# mbedUSBBorderRouter-V_1_0_0.net
KiCad netlist of a schematic drawn in EAGLE
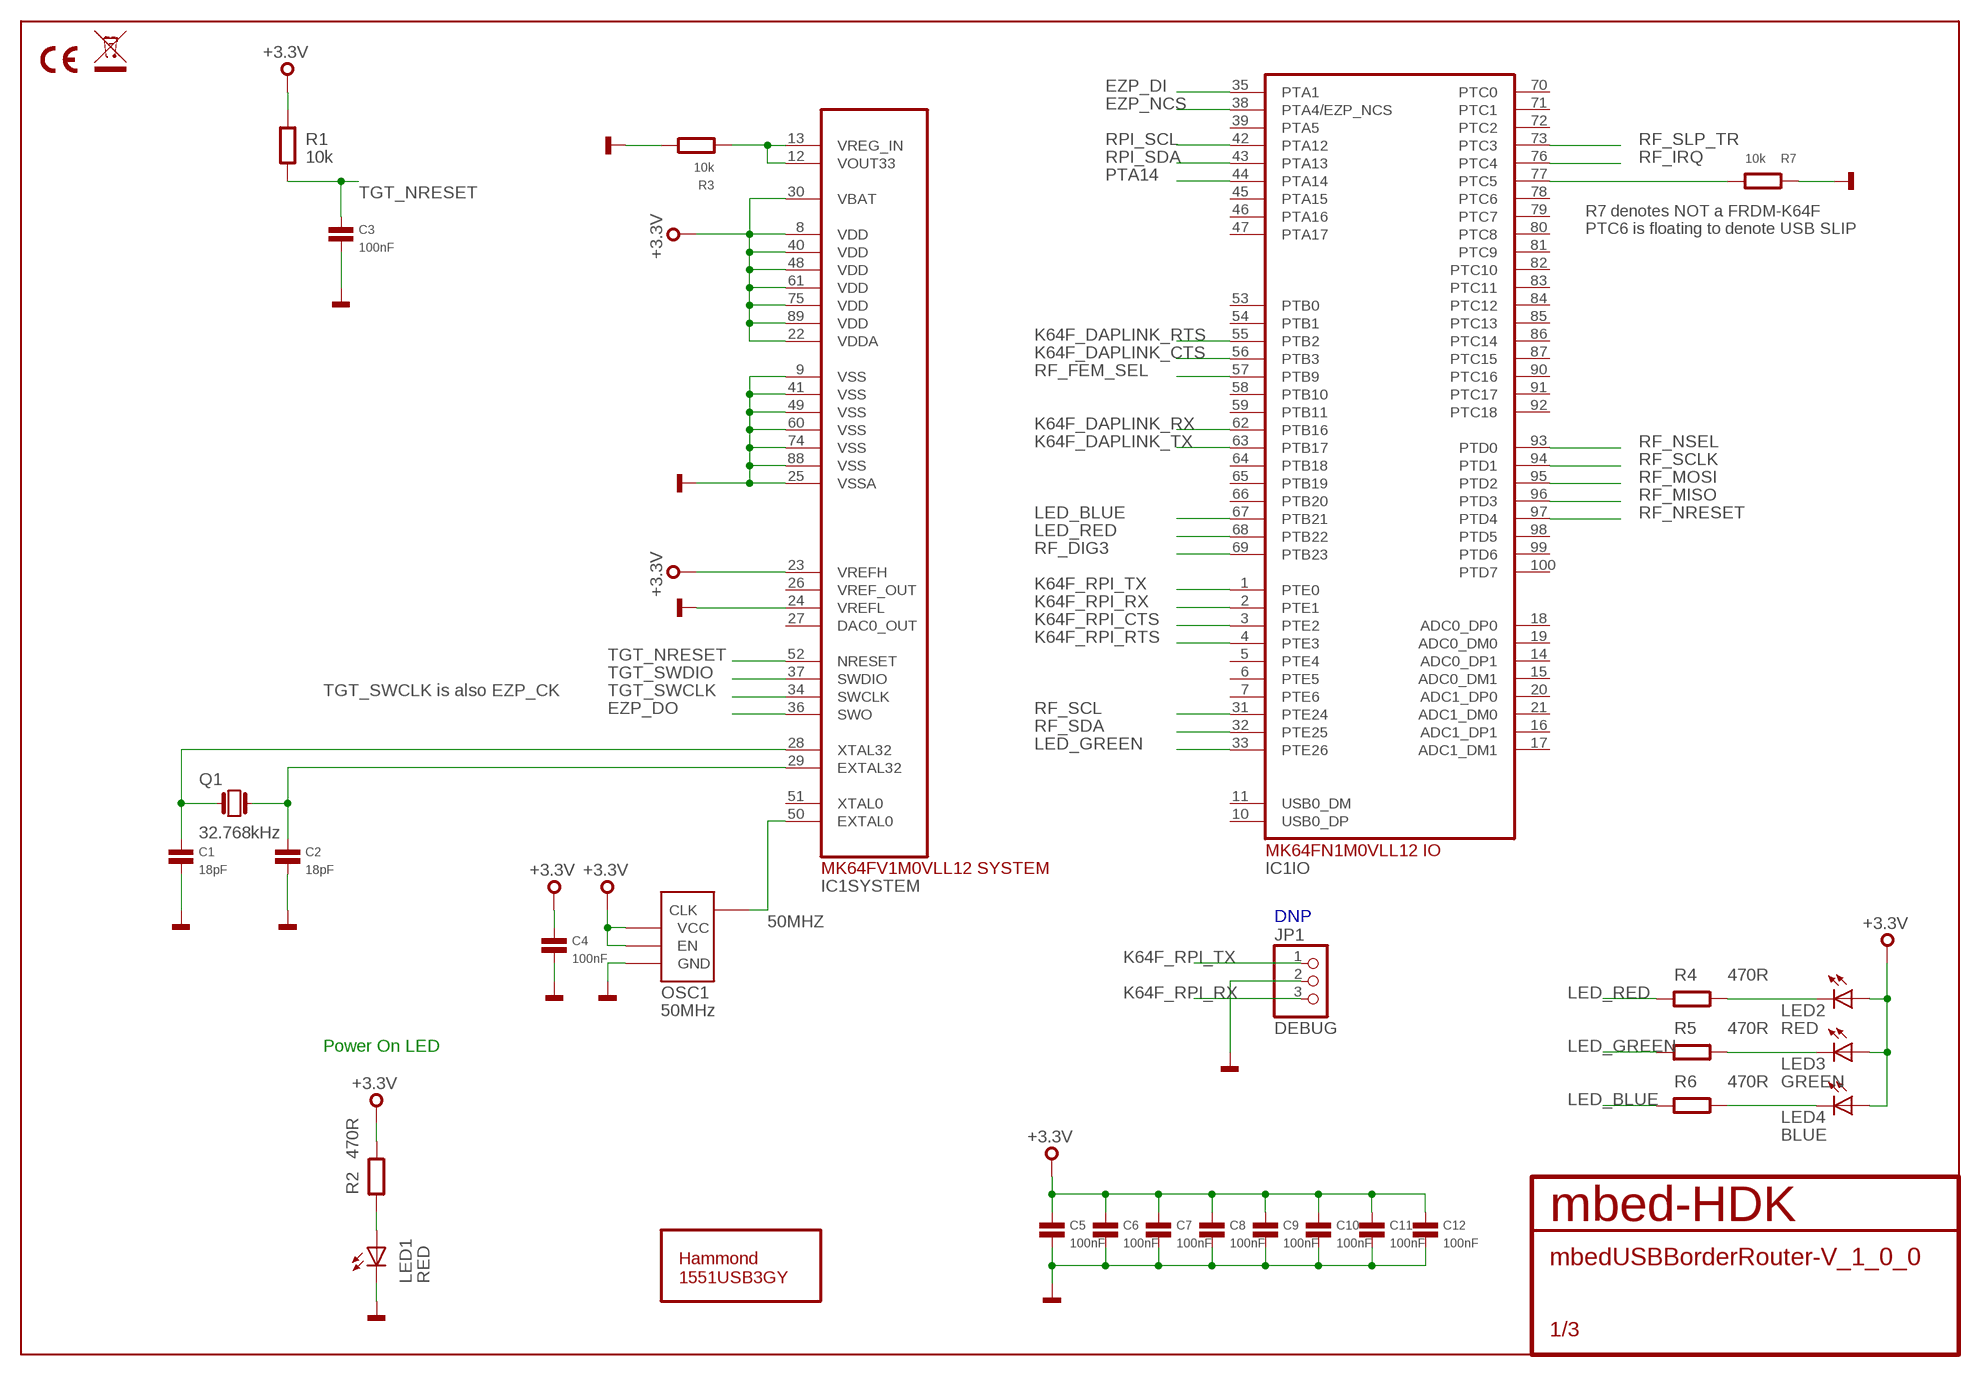
[diagram p0: schematic, sheet 1]
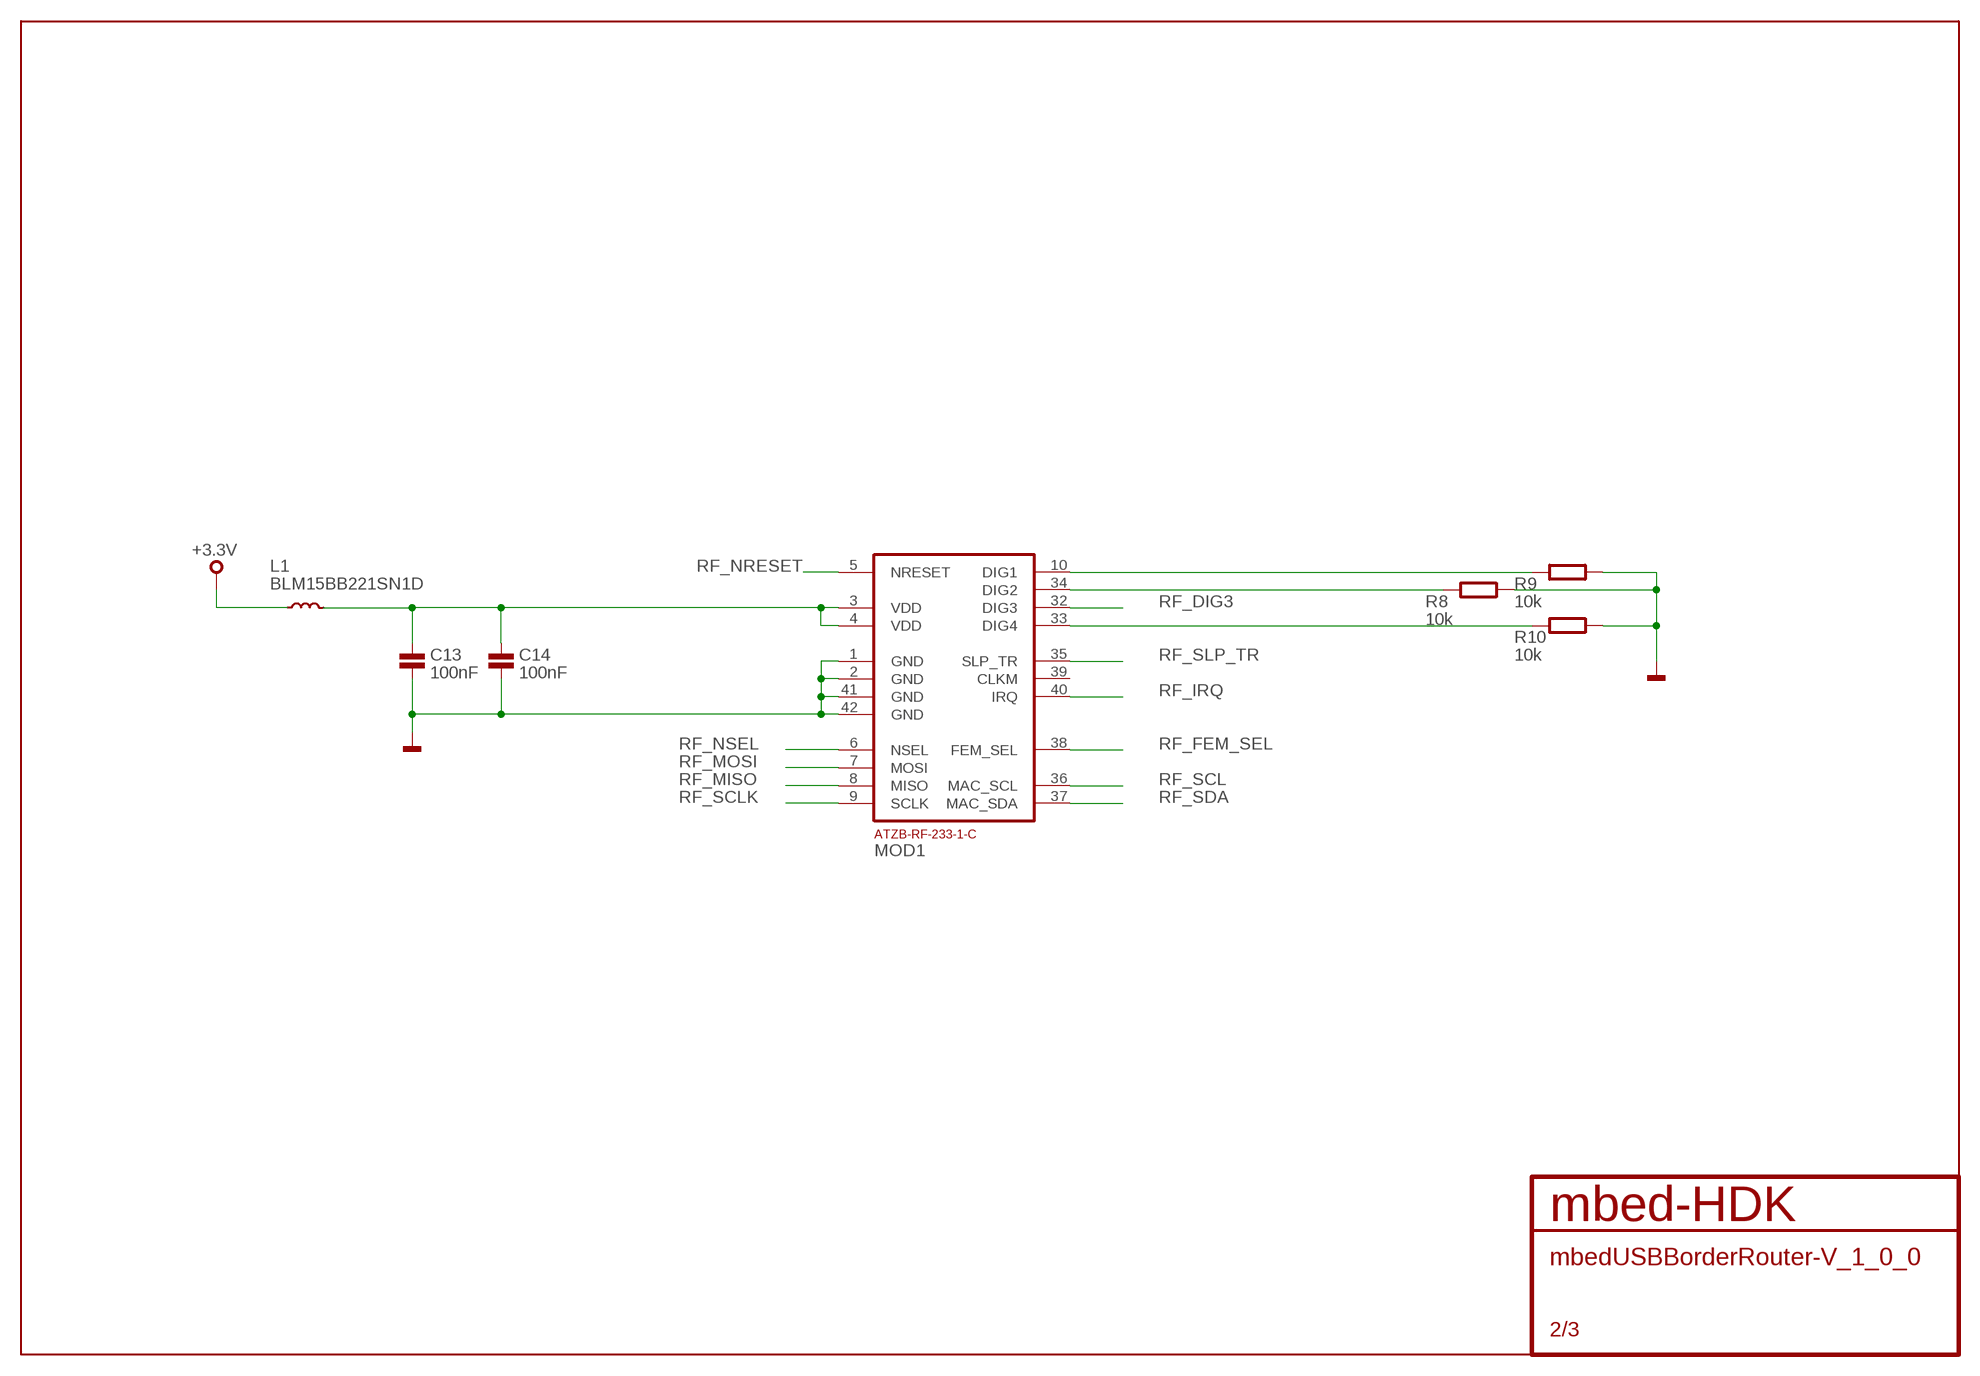
[diagram p1: schematic, sheet 2]
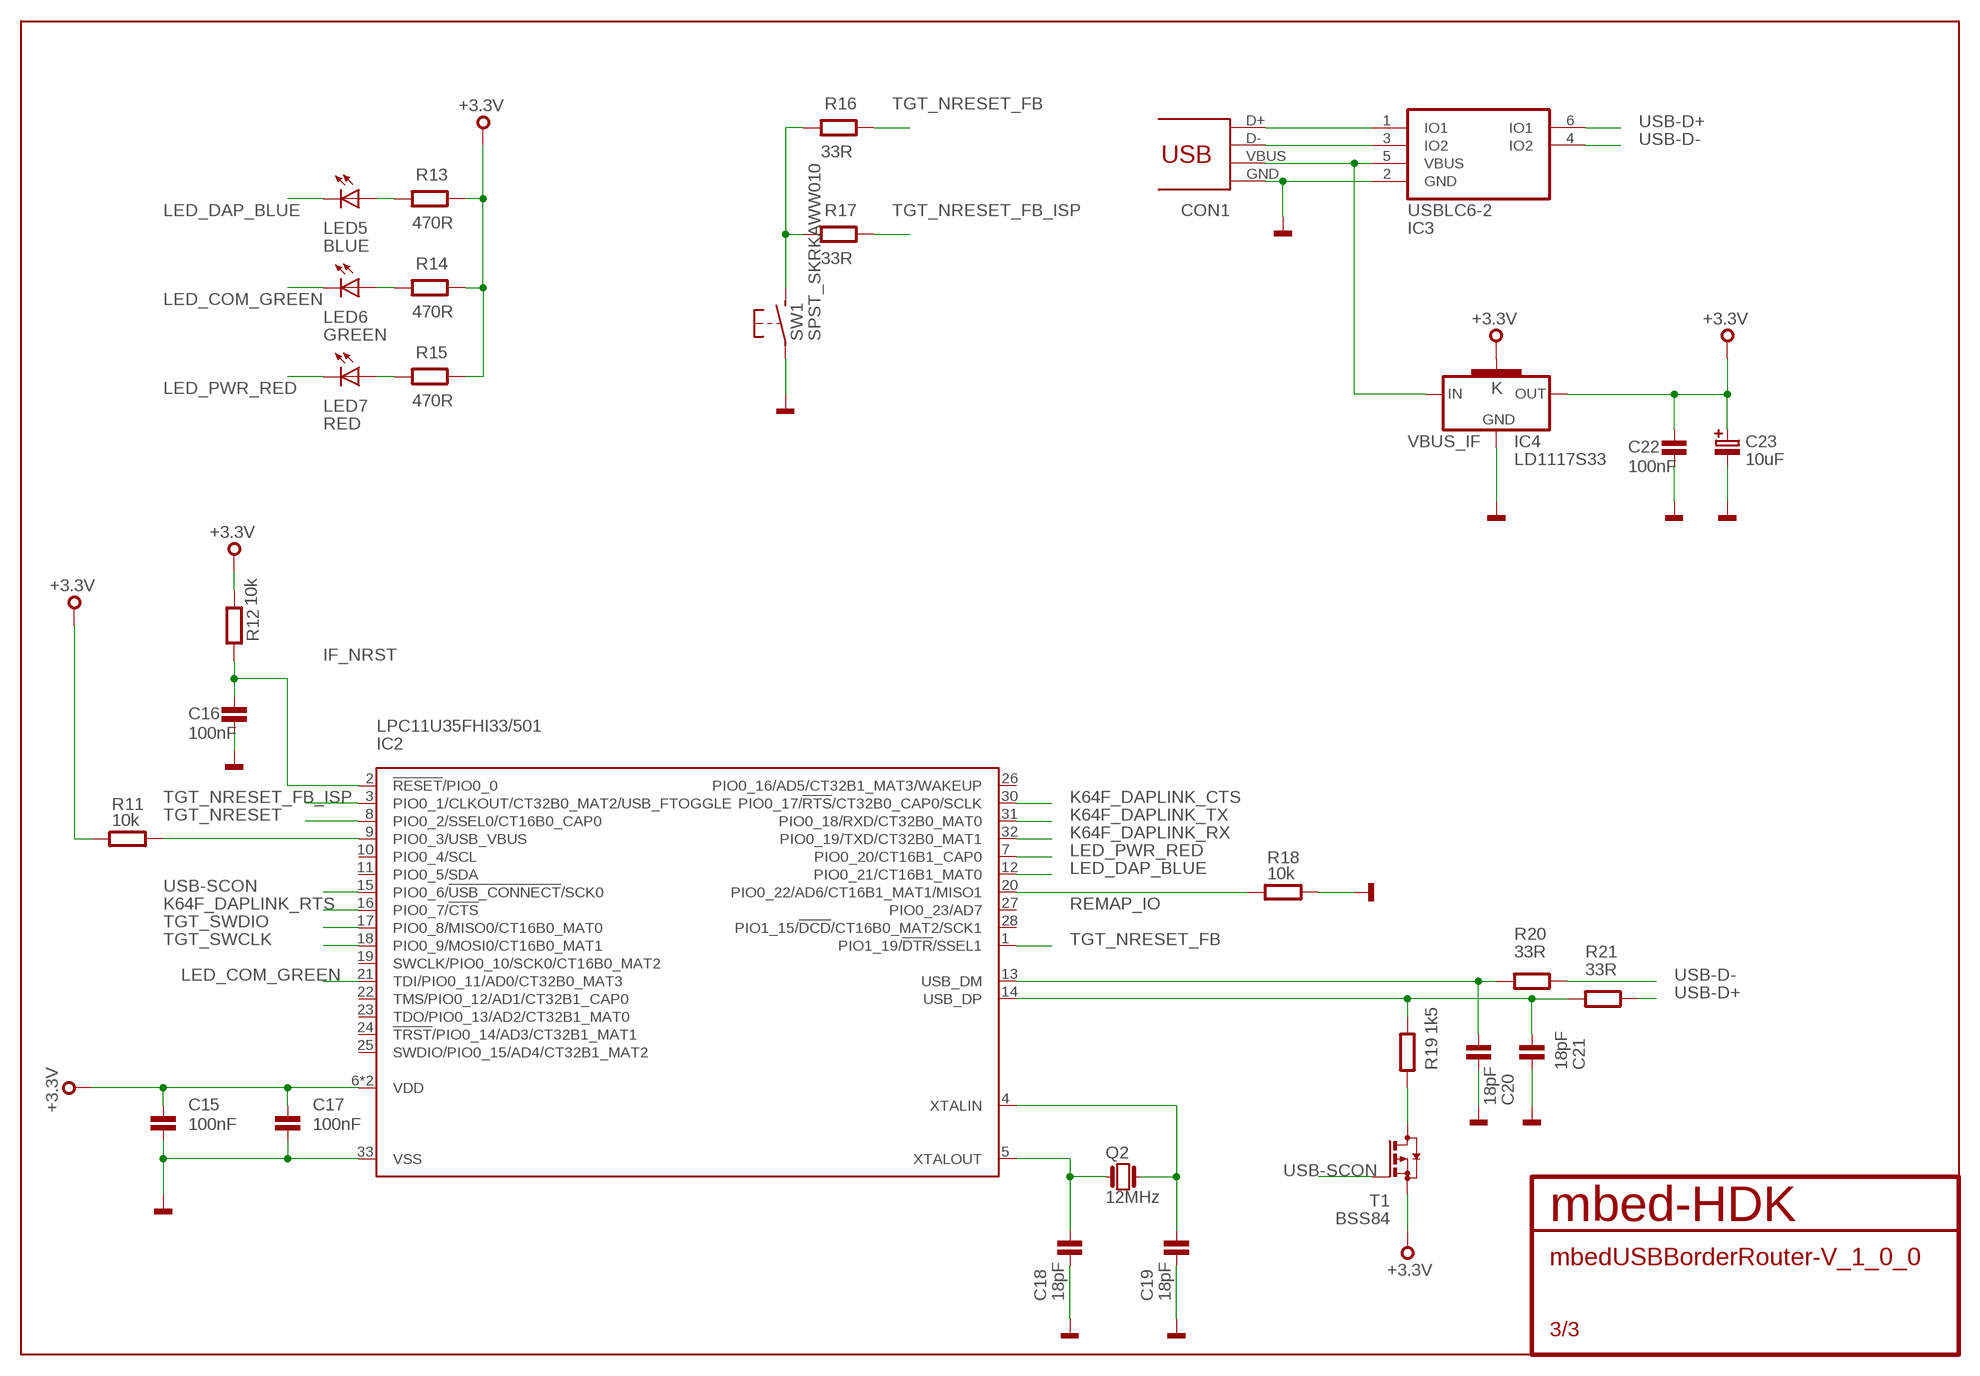
[diagram p2: schematic, sheet 3]

(export (version "E")
  (design (tool "Eeschema 10.0.6"))
  (components
    (comp (ref "C13")
      (value "100nF")
      (footprint "eagle-import:0402")
      (libsource (lib "eagle-import") (part "C0402"))
    )
    (comp (ref "C14")
      (value "100nF")
      (footprint "eagle-import:0402")
      (libsource (lib "eagle-import") (part "C0402"))
    )
    (comp (ref "L1")
      (value "BLM15BB221SN1D")
      (footprint "eagle-import:0402")
      (libsource (lib "eagle-import") (part "L0402"))
    )
    (comp (ref "MOD1")
      (value "ATZB-RF-233-1-C")
      (footprint "eagle-import:ATZB-RF-233-1-C")
      (libsource (lib "eagle-import") (part "ATZB-RF-233-1-C"))
    )
    (comp (ref "R8")
      (value "10k")
      (footprint "eagle-import:0402")
      (libsource (lib "eagle-import") (part "R0402"))
    )
    (comp (ref "R9")
      (value "10k")
      (footprint "eagle-import:0402")
      (libsource (lib "eagle-import") (part "R0402"))
    )
    (comp (ref "R10")
      (value "10k")
      (footprint "eagle-import:0402")
      (libsource (lib "eagle-import") (part "R0402"))
    )
    (comp (ref "C15")
      (value "100nF")
      (footprint "eagle-import:0402")
      (libsource (lib "eagle-import") (part "C0402"))
    )
    (comp (ref "C16")
      (value "100nF")
      (footprint "eagle-import:0402")
      (libsource (lib "eagle-import") (part "C0402"))
    )
    (comp (ref "C17")
      (value "100nF")
      (footprint "eagle-import:0402")
      (libsource (lib "eagle-import") (part "C0402"))
    )
    (comp (ref "C18")
      (value "18pF")
      (footprint "eagle-import:0402")
      (libsource (lib "eagle-import") (part "C0402"))
    )
    (comp (ref "C19")
      (value "18pF")
      (footprint "eagle-import:0402")
      (libsource (lib "eagle-import") (part "C0402"))
    )
    (comp (ref "C20")
      (value "18pF")
      (footprint "eagle-import:0402")
      (libsource (lib "eagle-import") (part "C0402"))
    )
    (comp (ref "C21")
      (value "18pF")
      (footprint "eagle-import:0402")
      (libsource (lib "eagle-import") (part "C0402"))
    )
    (comp (ref "C22")
      (value "100nF")
      (footprint "eagle-import:0402")
      (libsource (lib "eagle-import") (part "C0402"))
    )
    (comp (ref "C23")
      (value "10uF")
      (footprint "eagle-import:CASE-B")
      (libsource (lib "eagle-import") (part "C-POL_B"))
    )
    (comp (ref "CON1")
      (value "USB")
      (footprint "eagle-import:MOLEX-48037-2200")
      (libsource (lib "eagle-import") (part "USB"))
    )
    (comp (ref "IC2")
      (value "LPC11U35FHI33/501")
      (footprint "eagle-import:SOT617-3")
      (libsource (lib "eagle-import") (part "LPC11U35FHI33/501"))
    )
    (comp (ref "IC3")
      (value "USBLC6-2SC6")
      (footprint "eagle-import:SOT23-6L")
      (libsource (lib "eagle-import") (part "USBLC6-2SC6"))
    )
    (comp (ref "IC4")
      (value "LD1117S33")
      (footprint "eagle-import:SOT223")
      (libsource (lib "eagle-import") (part "LD1117S33"))
    )
    (comp (ref "LED5")
      (value "BLUE")
      (footprint "eagle-import:CHIPLED_0603")
      (libsource (lib "eagle-import") (part "LED0603"))
    )
    (comp (ref "LED6")
      (value "GREEN")
      (footprint "eagle-import:CHIPLED_0603")
      (libsource (lib "eagle-import") (part "LED0603"))
    )
    (comp (ref "LED7")
      (value "RED")
      (footprint "eagle-import:CHIPLED_0603")
      (libsource (lib "eagle-import") (part "LED0603"))
    )
    (comp (ref "Q2")
      (value "12MHz")
      (footprint "eagle-import:3.2X.2.5")
      (libsource (lib "eagle-import") (part "Q_3.2X2.5"))
    )
    (comp (ref "R11")
      (value "10k")
      (footprint "eagle-import:0402")
      (libsource (lib "eagle-import") (part "R0402"))
    )
    (comp (ref "R12")
      (value "10k")
      (footprint "eagle-import:0402")
      (libsource (lib "eagle-import") (part "R0402"))
    )
    (comp (ref "R13")
      (value "470R")
      (footprint "eagle-import:0402")
      (libsource (lib "eagle-import") (part "R0402"))
    )
    (comp (ref "R14")
      (value "470R")
      (footprint "eagle-import:0402")
      (libsource (lib "eagle-import") (part "R0402"))
    )
    (comp (ref "R15")
      (value "470R")
      (footprint "eagle-import:0402")
      (libsource (lib "eagle-import") (part "R0402"))
    )
    (comp (ref "R16")
      (value "33R")
      (footprint "eagle-import:0402")
      (libsource (lib "eagle-import") (part "R0402"))
    )
    (comp (ref "R17")
      (value "33R")
      (footprint "eagle-import:0402")
      (libsource (lib "eagle-import") (part "R0402"))
    )
    (comp (ref "R18")
      (value "10k")
      (footprint "eagle-import:0402")
      (libsource (lib "eagle-import") (part "R0402"))
    )
    (comp (ref "R19")
      (value "1k5")
      (footprint "eagle-import:0402")
      (libsource (lib "eagle-import") (part "R0402"))
    )
    (comp (ref "R20")
      (value "33R")
      (footprint "eagle-import:0402")
      (libsource (lib "eagle-import") (part "R0402"))
    )
    (comp (ref "R21")
      (value "33R")
      (footprint "eagle-import:0402")
      (libsource (lib "eagle-import") (part "R0402"))
    )
    (comp (ref "SW1")
      (value "SPST_SKRKAWW010")
      (footprint "eagle-import:SKRKAEE010")
      (libsource (lib "eagle-import") (part "SPST_SKRKAWW010"))
    )
    (comp (ref "T1")
      (value "BSS84")
      (footprint "eagle-import:SOT23")
      (libsource (lib "eagle-import") (part "BSS84"))
    )
    (comp (ref "BRD1")
      (value "HAMMOND-1551USB3GY")
      (footprint "eagle-import:HAMMOND-1551USB3GY")
      (libsource (lib "eagle-import") (part "HAMMOND-1551USB3GY"))
    )
    (comp (ref "C1")
      (value "18pF")
      (footprint "eagle-import:0402")
      (libsource (lib "eagle-import") (part "C0402"))
    )
    (comp (ref "C2")
      (value "18pF")
      (footprint "eagle-import:0402")
      (libsource (lib "eagle-import") (part "C0402"))
    )
    (comp (ref "C3")
      (value "100nF")
      (footprint "eagle-import:0402")
      (libsource (lib "eagle-import") (part "C0402"))
    )
    (comp (ref "C4")
      (value "100nF")
      (footprint "eagle-import:0402")
      (libsource (lib "eagle-import") (part "C0402"))
    )
    (comp (ref "C5")
      (value "100nF")
      (footprint "eagle-import:0402")
      (libsource (lib "eagle-import") (part "C0402"))
    )
    (comp (ref "C6")
      (value "100nF")
      (footprint "eagle-import:0402")
      (libsource (lib "eagle-import") (part "C0402"))
    )
    (comp (ref "C7")
      (value "100nF")
      (footprint "eagle-import:0402")
      (libsource (lib "eagle-import") (part "C0402"))
    )
    (comp (ref "C8")
      (value "100nF")
      (footprint "eagle-import:0402")
      (libsource (lib "eagle-import") (part "C0402"))
    )
    (comp (ref "C9")
      (value "100nF")
      (footprint "eagle-import:0402")
      (libsource (lib "eagle-import") (part "C0402"))
    )
    (comp (ref "C10")
      (value "100nF")
      (footprint "eagle-import:0402")
      (libsource (lib "eagle-import") (part "C0402"))
    )
    (comp (ref "C11")
      (value "100nF")
      (footprint "eagle-import:0402")
      (libsource (lib "eagle-import") (part "C0402"))
    )
    (comp (ref "C12")
      (value "100nF")
      (footprint "eagle-import:0402")
      (libsource (lib "eagle-import") (part "C0402"))
    )
    (comp (ref "IC1")
      (value "MK64FN1M0VLL12")
      (footprint "eagle-import:LQFP100")
      (libsource (lib "eagle-import") (part "MK64FN1M0VLL12"))
    )
    (comp (ref "JP1")
      (value "DEBUG")
      (footprint "eagle-import:1X03")
      (libsource (lib "eagle-import") (part "PINHD-1X3"))
    )
    (comp (ref "LED1")
      (value "RED")
      (footprint "eagle-import:CHIPLED_0603")
      (libsource (lib "eagle-import") (part "LED0603"))
    )
    (comp (ref "LED2")
      (value "RED")
      (footprint "eagle-import:CHIPLED_0603")
      (libsource (lib "eagle-import") (part "LED0603"))
    )
    (comp (ref "LED3")
      (value "GREEN")
      (footprint "eagle-import:CHIPLED_0603")
      (libsource (lib "eagle-import") (part "LED0603"))
    )
    (comp (ref "LED4")
      (value "BLUE")
      (footprint "eagle-import:CHIPLED_0603")
      (libsource (lib "eagle-import") (part "LED0603"))
    )
    (comp (ref "OSC1")
      (value "50MHz")
      (footprint "eagle-import:3.2X.2.5")
      (libsource (lib "eagle-import") (part "OSCILLATOR3.2X2.5"))
    )
    (comp (ref "Q1")
      (value "32.768kHz")
      (footprint "eagle-import:FC135")
      (libsource (lib "eagle-import") (part "Q_FC135"))
    )
    (comp (ref "R1")
      (value "10k")
      (footprint "eagle-import:0402")
      (libsource (lib "eagle-import") (part "R0402"))
    )
    (comp (ref "R2")
      (value "470R")
      (footprint "eagle-import:0402")
      (libsource (lib "eagle-import") (part "R0402"))
    )
    (comp (ref "R3")
      (value "10k")
      (footprint "eagle-import:0402")
      (libsource (lib "eagle-import") (part "R0402"))
    )
    (comp (ref "R4")
      (value "470R")
      (footprint "eagle-import:0402")
      (libsource (lib "eagle-import") (part "R0402"))
    )
    (comp (ref "R5")
      (value "470R")
      (footprint "eagle-import:0402")
      (libsource (lib "eagle-import") (part "R0402"))
    )
    (comp (ref "R6")
      (value "470R")
      (footprint "eagle-import:0402")
      (libsource (lib "eagle-import") (part "R0402"))
    )
    (comp (ref "R7")
      (value "10k")
      (footprint "eagle-import:0402")
      (libsource (lib "eagle-import") (part "R0402"))
    )
    (comp (ref "SS1")
      (value "CE-MARK")
      (footprint "eagle-import:CE-MARK-0.2")
      (libsource (lib "eagle-import") (part "CE-MARK"))
    )
    (comp (ref "SS2")
      (value "WEEE-MARK")
      (footprint "eagle-import:WEEE-MARK-0.2")
      (libsource (lib "eagle-import") (part "WEEE-MARK"))
    )
  )
  (nets
    (net (code "1") (name "+3.3V") (class "Default")
      (node (ref "C10") (pin "1") (pinfunction "P$1_1") (pintype "passive"))
      (node (ref "C11") (pin "1") (pinfunction "P$1_1") (pintype "passive"))
      (node (ref "C12") (pin "1") (pinfunction "P$1_1") (pintype "passive"))
      (node (ref "C15") (pin "1") (pinfunction "P$1_1") (pintype "passive"))
      (node (ref "C17") (pin "1") (pinfunction "P$1_1") (pintype "passive"))
      (node (ref "C22") (pin "1") (pinfunction "P$1_1") (pintype "passive"))
      (node (ref "C23") (pin "1") (pinfunction "1_1") (pintype "passive"))
      (node (ref "C4") (pin "1") (pinfunction "P$1_1") (pintype "passive"))
      (node (ref "C5") (pin "1") (pinfunction "P$1_1") (pintype "passive"))
      (node (ref "C6") (pin "1") (pinfunction "P$1_1") (pintype "passive"))
      (node (ref "C7") (pin "1") (pinfunction "P$1_1") (pintype "passive"))
      (node (ref "C8") (pin "1") (pinfunction "P$1_1") (pintype "passive"))
      (node (ref "C9") (pin "1") (pinfunction "P$1_1") (pintype "passive"))
      (node (ref "IC1") (pin "22") (pinfunction "VDDA_22") (pintype "bidirectional"))
      (node (ref "IC1") (pin "23") (pinfunction "VREFH_23") (pintype "bidirectional"))
      (node (ref "IC1") (pin "30") (pinfunction "VBAT_30") (pintype "bidirectional"))
      (node (ref "IC1") (pin "40") (pinfunction "VDD_40") (pintype "bidirectional"))
      (node (ref "IC1") (pin "48") (pinfunction "VDD_48") (pintype "bidirectional"))
      (node (ref "IC1") (pin "61") (pinfunction "VDD_61") (pintype "bidirectional"))
      (node (ref "IC1") (pin "75") (pinfunction "VDD_75") (pintype "bidirectional"))
      (node (ref "IC1") (pin "8") (pinfunction "VDD_8") (pintype "bidirectional"))
      (node (ref "IC1") (pin "89") (pinfunction "VDD_89") (pintype "bidirectional"))
      (node (ref "IC2") (pin "29") (pinfunction "VDD_29") (pintype "passive"))
      (node (ref "IC2") (pin "6") (pinfunction "VDD_6") (pintype "passive"))
      (node (ref "IC4") (pin "2") (pinfunction "OUT_2") (pintype "passive"))
      (node (ref "IC4") (pin "4") (pinfunction "K_4") (pintype "passive"))
      (node (ref "L1") (pin "1") (pinfunction "P$1_1") (pintype "bidirectional"))
      (node (ref "LED2") (pin "A") (pinfunction "A_A") (pintype "passive"))
      (node (ref "LED3") (pin "A") (pinfunction "A_A") (pintype "passive"))
      (node (ref "LED4") (pin "A") (pinfunction "A_A") (pintype "passive"))
      (node (ref "OSC1") (pin "P$1") (pinfunction "EN_P$1") (pintype "bidirectional"))
      (node (ref "OSC1") (pin "P$4") (pinfunction "VCC_P$4") (pintype "bidirectional"))
      (node (ref "R1") (pin "2") (pinfunction "P$2_2") (pintype "passive"))
      (node (ref "R11") (pin "2") (pinfunction "P$2_2") (pintype "passive"))
      (node (ref "R12") (pin "2") (pinfunction "P$2_2") (pintype "passive"))
      (node (ref "R13") (pin "1") (pinfunction "P$1_1") (pintype "passive"))
      (node (ref "R14") (pin "1") (pinfunction "P$1_1") (pintype "passive"))
      (node (ref "R15") (pin "1") (pinfunction "P$1_1") (pintype "passive"))
      (node (ref "R2") (pin "2") (pinfunction "P$2_2") (pintype "passive"))
      (node (ref "T1") (pin "2") (pinfunction "S_2") (pintype "passive"))
    )
    (net (code "2") (name "50MHZ") (class "Default")
      (node (ref "IC1") (pin "50") (pinfunction "EXTAL0_50") (pintype "bidirectional"))
      (node (ref "OSC1") (pin "P$3") (pinfunction "CLK_P$3") (pintype "bidirectional"))
    )
    (net (code "3") (name "EZP_DI") (class "Default")
      (node (ref "IC1") (pin "35") (pinfunction "PTA1_35") (pintype "bidirectional"))
    )
    (net (code "4") (name "EZP_DO") (class "Default")
      (node (ref "IC1") (pin "36") (pinfunction "SWO_36") (pintype "bidirectional"))
    )
    (net (code "5") (name "EZP_NCS") (class "Default")
      (node (ref "IC1") (pin "38") (pinfunction "PTA4/EZP_NCS_38") (pintype "bidirectional"))
    )
    (net (code "6") (name "GND") (class "Default")
      (node (ref "C1") (pin "2") (pinfunction "P$2_2") (pintype "passive"))
      (node (ref "C10") (pin "2") (pinfunction "P$2_2") (pintype "passive"))
      (node (ref "C11") (pin "2") (pinfunction "P$2_2") (pintype "passive"))
      (node (ref "C12") (pin "2") (pinfunction "P$2_2") (pintype "passive"))
      (node (ref "C13") (pin "2") (pinfunction "P$2_2") (pintype "passive"))
      (node (ref "C14") (pin "2") (pinfunction "P$2_2") (pintype "passive"))
      (node (ref "C15") (pin "2") (pinfunction "P$2_2") (pintype "passive"))
      (node (ref "C16") (pin "2") (pinfunction "P$2_2") (pintype "passive"))
      (node (ref "C17") (pin "2") (pinfunction "P$2_2") (pintype "passive"))
      (node (ref "C18") (pin "2") (pinfunction "P$2_2") (pintype "passive"))
      (node (ref "C19") (pin "2") (pinfunction "P$2_2") (pintype "passive"))
      (node (ref "C2") (pin "2") (pinfunction "P$2_2") (pintype "passive"))
      (node (ref "C20") (pin "2") (pinfunction "P$2_2") (pintype "passive"))
      (node (ref "C21") (pin "2") (pinfunction "P$2_2") (pintype "passive"))
      (node (ref "C22") (pin "2") (pinfunction "P$2_2") (pintype "passive"))
      (node (ref "C23") (pin "2") (pinfunction "2_2") (pintype "passive"))
      (node (ref "C3") (pin "2") (pinfunction "P$2_2") (pintype "passive"))
      (node (ref "C4") (pin "2") (pinfunction "P$2_2") (pintype "passive"))
      (node (ref "C5") (pin "2") (pinfunction "P$2_2") (pintype "passive"))
      (node (ref "C6") (pin "2") (pinfunction "P$2_2") (pintype "passive"))
      (node (ref "C7") (pin "2") (pinfunction "P$2_2") (pintype "passive"))
      (node (ref "C8") (pin "2") (pinfunction "P$2_2") (pintype "passive"))
      (node (ref "C9") (pin "2") (pinfunction "P$2_2") (pintype "passive"))
      (node (ref "CON1") (pin "GND") (pinfunction "GND_GND") (pintype "bidirectional"))
      (node (ref "IC1") (pin "24") (pinfunction "VREFL_24") (pintype "bidirectional"))
      (node (ref "IC1") (pin "25") (pinfunction "VSSA_25") (pintype "bidirectional"))
      (node (ref "IC1") (pin "41") (pinfunction "VSS_41") (pintype "bidirectional"))
      (node (ref "IC1") (pin "49") (pinfunction "VSS_49") (pintype "bidirectional"))
      (node (ref "IC1") (pin "60") (pinfunction "VSS_60") (pintype "bidirectional"))
      (node (ref "IC1") (pin "74") (pinfunction "VSS_74") (pintype "bidirectional"))
      (node (ref "IC1") (pin "88") (pinfunction "VSS_88") (pintype "bidirectional"))
      (node (ref "IC1") (pin "9") (pinfunction "VSS_9") (pintype "bidirectional"))
      (node (ref "IC2") (pin "33") (pinfunction "VSS_33") (pintype "passive"))
      (node (ref "IC3") (pin "2") (pinfunction "GND_2") (pintype "bidirectional"))
      (node (ref "IC4") (pin "1") (pinfunction "GND_1") (pintype "input"))
      (node (ref "JP1") (pin "2") (pinfunction "2_2") (pintype "passive"))
      (node (ref "LED1") (pin "C") (pinfunction "C_C") (pintype "passive"))
      (node (ref "MOD1") (pin "1") (pinfunction "GND_1") (pintype "bidirectional"))
      (node (ref "MOD1") (pin "2") (pinfunction "GND_2") (pintype "bidirectional"))
      (node (ref "MOD1") (pin "41") (pinfunction "GND_41") (pintype "bidirectional"))
      (node (ref "MOD1") (pin "42") (pinfunction "GND_42") (pintype "bidirectional"))
      (node (ref "OSC1") (pin "P$2") (pinfunction "GND_P$2") (pintype "bidirectional"))
      (node (ref "R10") (pin "1") (pinfunction "P$1_1") (pintype "passive"))
      (node (ref "R18") (pin "1") (pinfunction "P$1_1") (pintype "passive"))
      (node (ref "R3") (pin "2") (pinfunction "P$2_2") (pintype "passive"))
      (node (ref "R7") (pin "2") (pinfunction "P$2_2") (pintype "passive"))
      (node (ref "R8") (pin "2") (pinfunction "P$2_2") (pintype "passive"))
      (node (ref "R9") (pin "2") (pinfunction "P$2_2") (pintype "passive"))
      (node (ref "SW1") (pin "P$1") (pinfunction "P_P$1") (pintype "passive"))
    )
    (net (code "7") (name "IF_NRST") (class "Default")
      (node (ref "C16") (pin "1") (pinfunction "P$1_1") (pintype "passive"))
      (node (ref "IC2") (pin "2") (pinfunction "~{RESET}/PIO0_0_2") (pintype "bidirectional"))
      (node (ref "R12") (pin "1") (pinfunction "P$1_1") (pintype "passive"))
    )
    (net (code "8") (name "K64F_DAPLINK_CTS") (class "Default")
      (node (ref "IC1") (pin "56") (pinfunction "PTB3_56") (pintype "bidirectional"))
      (node (ref "IC2") (pin "30") (pinfunction "PIO0_17/~{RTS}/CT32B0_CAP0/SCLK_30") (pintype "bidirectional"))
    )
    (net (code "9") (name "K64F_DAPLINK_RTS") (class "Default")
      (node (ref "IC1") (pin "55") (pinfunction "PTB2_55") (pintype "bidirectional"))
      (node (ref "IC2") (pin "16") (pinfunction "PIO0_7/~{CTS}_16") (pintype "bidirectional"))
    )
    (net (code "10") (name "K64F_DAPLINK_RX") (class "Default")
      (node (ref "IC1") (pin "62") (pinfunction "PTB16_62") (pintype "bidirectional"))
      (node (ref "IC2") (pin "32") (pinfunction "PIO0_19/TXD/CT32B0_MAT1_32") (pintype "bidirectional"))
    )
    (net (code "11") (name "K64F_DAPLINK_TX") (class "Default")
      (node (ref "IC1") (pin "63") (pinfunction "PTB17_63") (pintype "bidirectional"))
      (node (ref "IC2") (pin "31") (pinfunction "PIO0_18/RXD/CT32B0_MAT0_31") (pintype "bidirectional"))
    )
    (net (code "12") (name "K64F_RPI_CTS") (class "Default")
      (node (ref "IC1") (pin "3") (pinfunction "PTE2_3") (pintype "bidirectional"))
    )
    (net (code "13") (name "K64F_RPI_RTS") (class "Default")
      (node (ref "IC1") (pin "4") (pinfunction "PTE3_4") (pintype "bidirectional"))
    )
    (net (code "14") (name "K64F_RPI_RX") (class "Default")
      (node (ref "IC1") (pin "2") (pinfunction "PTE1_2") (pintype "bidirectional"))
      (node (ref "JP1") (pin "3") (pinfunction "3_3") (pintype "passive"))
    )
    (net (code "15") (name "K64F_RPI_TX") (class "Default")
      (node (ref "IC1") (pin "1") (pinfunction "PTE0_1") (pintype "bidirectional"))
      (node (ref "JP1") (pin "1") (pinfunction "1_1") (pintype "passive"))
    )
    (net (code "16") (name "LED_BLUE") (class "Default")
      (node (ref "IC1") (pin "67") (pinfunction "PTB21_67") (pintype "bidirectional"))
      (node (ref "R6") (pin "1") (pinfunction "P$1_1") (pintype "passive"))
    )
    (net (code "17") (name "LED_COM_GREEN") (class "Default")
      (node (ref "IC2") (pin "21") (pinfunction "TDI/PIO0_11/AD0/CT32B0_MAT3_21") (pintype "bidirectional"))
      (node (ref "LED6") (pin "C") (pinfunction "C_C") (pintype "passive"))
    )
    (net (code "18") (name "LED_DAP_BLUE") (class "Default")
      (node (ref "IC2") (pin "12") (pinfunction "PIO0_21/CT16B1_MAT0_12") (pintype "bidirectional"))
      (node (ref "LED5") (pin "C") (pinfunction "C_C") (pintype "passive"))
    )
    (net (code "19") (name "LED_GREEN") (class "Default")
      (node (ref "IC1") (pin "33") (pinfunction "PTE26_33") (pintype "bidirectional"))
      (node (ref "R5") (pin "1") (pinfunction "P$1_1") (pintype "passive"))
    )
    (net (code "20") (name "LED_PWR_RED") (class "Default")
      (node (ref "IC2") (pin "7") (pinfunction "PIO0_20/CT16B1_CAP0_7") (pintype "bidirectional"))
      (node (ref "LED7") (pin "C") (pinfunction "C_C") (pintype "passive"))
    )
    (net (code "21") (name "LED_RED") (class "Default")
      (node (ref "IC1") (pin "68") (pinfunction "PTB22_68") (pintype "bidirectional"))
      (node (ref "R4") (pin "1") (pinfunction "P$1_1") (pintype "passive"))
    )
    (net (code "22") (name "Net-(C1-P$1)") (class "Default")
      (node (ref "C1") (pin "1") (pinfunction "P$1_1") (pintype "passive"))
      (node (ref "IC1") (pin "28") (pinfunction "XTAL32_28") (pintype "bidirectional"))
      (node (ref "Q1") (pin "X1") (pinfunction "1_X1") (pintype "passive"))
    )
    (net (code "23") (name "Net-(C2-P$1)") (class "Default")
      (node (ref "C2") (pin "1") (pinfunction "P$1_1") (pintype "passive"))
      (node (ref "IC1") (pin "29") (pinfunction "EXTAL32_29") (pintype "bidirectional"))
      (node (ref "Q1") (pin "X2") (pinfunction "2_X2") (pintype "passive"))
    )
    (net (code "24") (name "Net-(C13-P$1)") (class "Default")
      (node (ref "C13") (pin "1") (pinfunction "P$1_1") (pintype "passive"))
      (node (ref "C14") (pin "1") (pinfunction "P$1_1") (pintype "passive"))
      (node (ref "L1") (pin "2") (pinfunction "P$2_2") (pintype "bidirectional"))
      (node (ref "MOD1") (pin "3") (pinfunction "VDD_3") (pintype "bidirectional"))
      (node (ref "MOD1") (pin "4") (pinfunction "VDD_4") (pintype "bidirectional"))
    )
    (net (code "25") (name "Net-(C18-P$1)") (class "Default")
      (node (ref "C18") (pin "1") (pinfunction "P$1_1") (pintype "passive"))
      (node (ref "IC2") (pin "5") (pinfunction "XTALOUT_5") (pintype "output"))
      (node (ref "Q2") (pin "P$1") (pinfunction "1_P$1") (pintype "passive"))
    )
    (net (code "26") (name "Net-(C19-P$1)") (class "Default")
      (node (ref "C19") (pin "1") (pinfunction "P$1_1") (pintype "passive"))
      (node (ref "IC2") (pin "4") (pinfunction "XTALIN_4") (pintype "input"))
      (node (ref "Q2") (pin "P$3") (pinfunction "2_P$3") (pintype "passive"))
    )
    (net (code "27") (name "Net-(C20-P$1)") (class "Default")
      (node (ref "C20") (pin "1") (pinfunction "P$1_1") (pintype "passive"))
      (node (ref "IC2") (pin "13") (pinfunction "USB_DM_13") (pintype "bidirectional"))
      (node (ref "R20") (pin "2") (pinfunction "P$2_2") (pintype "passive"))
    )
    (net (code "28") (name "Net-(C21-P$1)") (class "Default")
      (node (ref "C21") (pin "1") (pinfunction "P$1_1") (pintype "passive"))
      (node (ref "IC2") (pin "14") (pinfunction "USB_DP_14") (pintype "bidirectional"))
      (node (ref "R19") (pin "2") (pinfunction "P$2_2") (pintype "passive"))
      (node (ref "R21") (pin "2") (pinfunction "P$2_2") (pintype "passive"))
    )
    (net (code "29") (name "Net-(CON1-PadD+)") (class "Default")
      (node (ref "CON1") (pin "D+") (pinfunction "D+_D+") (pintype "bidirectional"))
      (node (ref "IC3") (pin "1") (pinfunction "IO1_1") (pintype "bidirectional"))
    )
    (net (code "30") (name "Net-(CON1-PadD-)") (class "Default")
      (node (ref "CON1") (pin "D-") (pinfunction "D-_D-") (pintype "bidirectional"))
      (node (ref "IC3") (pin "3") (pinfunction "IO2_3") (pintype "bidirectional"))
    )
    (net (code "31") (name "Net-(IC1A-PTC5)") (class "Default")
      (node (ref "IC1") (pin "77") (pinfunction "PTC5_77") (pintype "bidirectional"))
      (node (ref "R7") (pin "1") (pinfunction "P$1_1") (pintype "passive"))
    )
    (net (code "32") (name "Net-(IC1B-VOUT33)") (class "Default")
      (node (ref "IC1") (pin "12") (pinfunction "VOUT33_12") (pintype "bidirectional"))
      (node (ref "IC1") (pin "13") (pinfunction "VREG_IN_13") (pintype "bidirectional"))
      (node (ref "R3") (pin "1") (pinfunction "P$1_1") (pintype "passive"))
    )
    (net (code "33") (name "Net-(IC2-PIO0_3{slash}USB_VBUS)") (class "Default")
      (node (ref "IC2") (pin "9") (pinfunction "PIO0_3/USB_VBUS_9") (pintype "bidirectional"))
      (node (ref "R11") (pin "1") (pinfunction "P$1_1") (pintype "passive"))
    )
    (net (code "34") (name "Net-(MOD1-DIG1)") (class "Default")
      (node (ref "MOD1") (pin "10") (pinfunction "DIG1_10") (pintype "bidirectional"))
      (node (ref "R9") (pin "1") (pinfunction "P$1_1") (pintype "passive"))
    )
    (net (code "35") (name "Net-(MOD1-DIG2)") (class "Default")
      (node (ref "MOD1") (pin "34") (pinfunction "DIG2_34") (pintype "bidirectional"))
      (node (ref "R8") (pin "1") (pinfunction "P$1_1") (pintype "passive"))
    )
    (net (code "36") (name "Net-(MOD1-DIG4)") (class "Default")
      (node (ref "MOD1") (pin "33") (pinfunction "DIG4_33") (pintype "bidirectional"))
      (node (ref "R10") (pin "2") (pinfunction "P$2_2") (pintype "passive"))
    )
    (net (code "37") (name "Net-(R2-P$1)") (class "Default")
      (node (ref "LED1") (pin "A") (pinfunction "A_A") (pintype "passive"))
      (node (ref "R2") (pin "1") (pinfunction "P$1_1") (pintype "passive"))
    )
    (net (code "38") (name "Net-(R4-P$2)") (class "Default")
      (node (ref "LED2") (pin "C") (pinfunction "C_C") (pintype "passive"))
      (node (ref "R4") (pin "2") (pinfunction "P$2_2") (pintype "passive"))
    )
    (net (code "39") (name "Net-(R5-P$2)") (class "Default")
      (node (ref "LED3") (pin "C") (pinfunction "C_C") (pintype "passive"))
      (node (ref "R5") (pin "2") (pinfunction "P$2_2") (pintype "passive"))
    )
    (net (code "40") (name "Net-(R6-P$2)") (class "Default")
      (node (ref "LED4") (pin "C") (pinfunction "C_C") (pintype "passive"))
      (node (ref "R6") (pin "2") (pinfunction "P$2_2") (pintype "passive"))
    )
    (net (code "41") (name "Net-(R13-P$2)") (class "Default")
      (node (ref "LED5") (pin "A") (pinfunction "A_A") (pintype "passive"))
      (node (ref "R13") (pin "2") (pinfunction "P$2_2") (pintype "passive"))
    )
    (net (code "42") (name "Net-(R14-P$2)") (class "Default")
      (node (ref "LED6") (pin "A") (pinfunction "A_A") (pintype "passive"))
      (node (ref "R14") (pin "2") (pinfunction "P$2_2") (pintype "passive"))
    )
    (net (code "43") (name "Net-(R15-P$2)") (class "Default")
      (node (ref "LED7") (pin "A") (pinfunction "A_A") (pintype "passive"))
      (node (ref "R15") (pin "2") (pinfunction "P$2_2") (pintype "passive"))
    )
    (net (code "44") (name "Net-(R16-P$2)") (class "Default")
      (node (ref "R16") (pin "2") (pinfunction "P$2_2") (pintype "passive"))
      (node (ref "R17") (pin "2") (pinfunction "P$2_2") (pintype "passive"))
      (node (ref "SW1") (pin "P$2") (pinfunction "S_P$2") (pintype "passive"))
    )
    (net (code "45") (name "Net-(R19-P$1)") (class "Default")
      (node (ref "R19") (pin "1") (pinfunction "P$1_1") (pintype "passive"))
      (node (ref "T1") (pin "3") (pinfunction "D_3") (pintype "passive"))
    )
    (net (code "46") (name "PTA14") (class "Default")
      (node (ref "IC1") (pin "44") (pinfunction "PTA14_44") (pintype "bidirectional"))
    )
    (net (code "47") (name "REMAP_IO") (class "Default")
      (node (ref "IC2") (pin "20") (pinfunction "PIO0_22/AD6/CT16B1_MAT1/MISO1_20") (pintype "bidirectional"))
      (node (ref "R18") (pin "2") (pinfunction "P$2_2") (pintype "passive"))
    )
    (net (code "48") (name "RF_DIG3") (class "Default")
      (node (ref "IC1") (pin "69") (pinfunction "PTB23_69") (pintype "bidirectional"))
      (node (ref "MOD1") (pin "32") (pinfunction "DIG3_32") (pintype "bidirectional"))
    )
    (net (code "49") (name "RF_FEM_SEL") (class "Default")
      (node (ref "IC1") (pin "57") (pinfunction "PTB9_57") (pintype "bidirectional"))
      (node (ref "MOD1") (pin "38") (pinfunction "FEM_SEL_38") (pintype "bidirectional"))
    )
    (net (code "50") (name "RF_IRQ") (class "Default")
      (node (ref "IC1") (pin "76") (pinfunction "PTC4_76") (pintype "bidirectional"))
      (node (ref "MOD1") (pin "40") (pinfunction "IRQ_40") (pintype "bidirectional"))
    )
    (net (code "51") (name "RF_MISO") (class "Default")
      (node (ref "IC1") (pin "96") (pinfunction "PTD3_96") (pintype "bidirectional"))
      (node (ref "MOD1") (pin "8") (pinfunction "MISO_8") (pintype "bidirectional"))
    )
    (net (code "52") (name "RF_MOSI") (class "Default")
      (node (ref "IC1") (pin "95") (pinfunction "PTD2_95") (pintype "bidirectional"))
      (node (ref "MOD1") (pin "7") (pinfunction "MOSI_7") (pintype "bidirectional"))
    )
    (net (code "53") (name "RF_NRESET") (class "Default")
      (node (ref "IC1") (pin "97") (pinfunction "PTD4_97") (pintype "bidirectional"))
      (node (ref "MOD1") (pin "5") (pinfunction "NRESET_5") (pintype "bidirectional"))
    )
    (net (code "54") (name "RF_NSEL") (class "Default")
      (node (ref "IC1") (pin "93") (pinfunction "PTD0_93") (pintype "bidirectional"))
      (node (ref "MOD1") (pin "6") (pinfunction "NSEL_6") (pintype "bidirectional"))
    )
    (net (code "55") (name "RF_SCL") (class "Default")
      (node (ref "IC1") (pin "31") (pinfunction "PTE24_31") (pintype "bidirectional"))
      (node (ref "MOD1") (pin "36") (pinfunction "MAC_SCL_36") (pintype "bidirectional"))
    )
    (net (code "56") (name "RF_SCLK") (class "Default")
      (node (ref "IC1") (pin "94") (pinfunction "PTD1_94") (pintype "bidirectional"))
      (node (ref "MOD1") (pin "9") (pinfunction "SCLK_9") (pintype "bidirectional"))
    )
    (net (code "57") (name "RF_SDA") (class "Default")
      (node (ref "IC1") (pin "32") (pinfunction "PTE25_32") (pintype "bidirectional"))
      (node (ref "MOD1") (pin "37") (pinfunction "MAC_SDA_37") (pintype "bidirectional"))
    )
    (net (code "58") (name "RF_SLP_TR") (class "Default")
      (node (ref "IC1") (pin "73") (pinfunction "PTC3_73") (pintype "bidirectional"))
      (node (ref "MOD1") (pin "35") (pinfunction "SLP_TR_35") (pintype "bidirectional"))
    )
    (net (code "59") (name "RPI_SCL") (class "Default")
      (node (ref "IC1") (pin "42") (pinfunction "PTA12_42") (pintype "bidirectional"))
    )
    (net (code "60") (name "RPI_SDA") (class "Default")
      (node (ref "IC1") (pin "43") (pinfunction "PTA13_43") (pintype "bidirectional"))
    )
    (net (code "61") (name "TGT_NRESET") (class "Default")
      (node (ref "C3") (pin "1") (pinfunction "P$1_1") (pintype "passive"))
      (node (ref "IC1") (pin "52") (pinfunction "NRESET_52") (pintype "bidirectional"))
      (node (ref "IC2") (pin "8") (pinfunction "PIO0_2/SSEL0/CT16B0_CAP0_8") (pintype "bidirectional"))
      (node (ref "R1") (pin "1") (pinfunction "P$1_1") (pintype "passive"))
    )
    (net (code "62") (name "TGT_NRESET_FB") (class "Default")
      (node (ref "IC2") (pin "1") (pinfunction "PIO1_19/~{DTR}/SSEL1_1") (pintype "bidirectional"))
      (node (ref "R16") (pin "1") (pinfunction "P$1_1") (pintype "passive"))
    )
    (net (code "63") (name "TGT_NRESET_FB_ISP") (class "Default")
      (node (ref "IC2") (pin "3") (pinfunction "PIO0_1/CLKOUT/CT32B0_MAT2/USB_FTOGGLE_3") (pintype "bidirectional"))
      (node (ref "R17") (pin "1") (pinfunction "P$1_1") (pintype "passive"))
    )
    (net (code "64") (name "TGT_SWCLK") (class "Default")
      (node (ref "IC1") (pin "34") (pinfunction "SWCLK_34") (pintype "bidirectional"))
      (node (ref "IC2") (pin "18") (pinfunction "PIO0_9/MOSI0/CT16B0_MAT1_18") (pintype "bidirectional"))
    )
    (net (code "65") (name "TGT_SWDIO") (class "Default")
      (node (ref "IC1") (pin "37") (pinfunction "SWDIO_37") (pintype "bidirectional"))
      (node (ref "IC2") (pin "17") (pinfunction "PIO0_8/MISO0/CT16B0_MAT0_17") (pintype "bidirectional"))
    )
    (net (code "66") (name "USB-D+") (class "Default")
      (node (ref "IC3") (pin "6") (pinfunction "IO1_6") (pintype "bidirectional"))
      (node (ref "R21") (pin "1") (pinfunction "P$1_1") (pintype "passive"))
    )
    (net (code "67") (name "USB-D-") (class "Default")
      (node (ref "IC3") (pin "4") (pinfunction "IO2_4") (pintype "bidirectional"))
      (node (ref "R20") (pin "1") (pinfunction "P$1_1") (pintype "passive"))
    )
    (net (code "68") (name "USB-SCON") (class "Default")
      (node (ref "IC2") (pin "15") (pinfunction "PIO0_6/~{USB_CONNECT}/SCK0_15") (pintype "bidirectional"))
      (node (ref "T1") (pin "1") (pinfunction "G_1") (pintype "passive"))
    )
    (net (code "69") (name "VBUS_IF") (class "Default")
      (node (ref "CON1") (pin "VBUS") (pinfunction "VBUS_VBUS") (pintype "bidirectional"))
      (node (ref "IC3") (pin "5") (pinfunction "VBUS_5") (pintype "bidirectional"))
      (node (ref "IC4") (pin "3") (pinfunction "IN_3") (pintype "input"))
    )
    (net (code "70") (name "unconnected-(IC1A-ADC0_DM0-Pad19)") (class "Default")
      (node (ref "IC1") (pin "19") (pinfunction "ADC0_DM0_19") (pintype "bidirectional"))
    )
    (net (code "71") (name "unconnected-(IC1A-ADC0_DM1-Pad15)") (class "Default")
      (node (ref "IC1") (pin "15") (pinfunction "ADC0_DM1_15") (pintype "bidirectional"))
    )
    (net (code "72") (name "unconnected-(IC1A-ADC0_DP0-Pad18)") (class "Default")
      (node (ref "IC1") (pin "18") (pinfunction "ADC0_DP0_18") (pintype "bidirectional"))
    )
    (net (code "73") (name "unconnected-(IC1A-ADC0_DP1-Pad14)") (class "Default")
      (node (ref "IC1") (pin "14") (pinfunction "ADC0_DP1_14") (pintype "bidirectional"))
    )
    (net (code "74") (name "unconnected-(IC1A-ADC1_DM0-Pad21)") (class "Default")
      (node (ref "IC1") (pin "21") (pinfunction "ADC1_DM0_21") (pintype "bidirectional"))
    )
    (net (code "75") (name "unconnected-(IC1A-ADC1_DM1-Pad17)") (class "Default")
      (node (ref "IC1") (pin "17") (pinfunction "ADC1_DM1_17") (pintype "bidirectional"))
    )
    (net (code "76") (name "unconnected-(IC1A-ADC1_DP0-Pad20)") (class "Default")
      (node (ref "IC1") (pin "20") (pinfunction "ADC1_DP0_20") (pintype "bidirectional"))
    )
    (net (code "77") (name "unconnected-(IC1A-ADC1_DP1-Pad16)") (class "Default")
      (node (ref "IC1") (pin "16") (pinfunction "ADC1_DP1_16") (pintype "bidirectional"))
    )
    (net (code "78") (name "unconnected-(IC1A-PTA5-Pad39)") (class "Default")
      (node (ref "IC1") (pin "39") (pinfunction "PTA5_39") (pintype "bidirectional"))
    )
    (net (code "79") (name "unconnected-(IC1A-PTA15-Pad45)") (class "Default")
      (node (ref "IC1") (pin "45") (pinfunction "PTA15_45") (pintype "bidirectional"))
    )
    (net (code "80") (name "unconnected-(IC1A-PTA16-Pad46)") (class "Default")
      (node (ref "IC1") (pin "46") (pinfunction "PTA16_46") (pintype "bidirectional"))
    )
    (net (code "81") (name "unconnected-(IC1A-PTA17-Pad47)") (class "Default")
      (node (ref "IC1") (pin "47") (pinfunction "PTA17_47") (pintype "bidirectional"))
    )
    (net (code "82") (name "unconnected-(IC1A-PTB0-Pad53)") (class "Default")
      (node (ref "IC1") (pin "53") (pinfunction "PTB0_53") (pintype "bidirectional"))
    )
    (net (code "83") (name "unconnected-(IC1A-PTB1-Pad54)") (class "Default")
      (node (ref "IC1") (pin "54") (pinfunction "PTB1_54") (pintype "bidirectional"))
    )
    (net (code "84") (name "unconnected-(IC1A-PTB10-Pad58)") (class "Default")
      (node (ref "IC1") (pin "58") (pinfunction "PTB10_58") (pintype "bidirectional"))
    )
    (net (code "85") (name "unconnected-(IC1A-PTB11-Pad59)") (class "Default")
      (node (ref "IC1") (pin "59") (pinfunction "PTB11_59") (pintype "bidirectional"))
    )
    (net (code "86") (name "unconnected-(IC1A-PTB18-Pad64)") (class "Default")
      (node (ref "IC1") (pin "64") (pinfunction "PTB18_64") (pintype "bidirectional"))
    )
    (net (code "87") (name "unconnected-(IC1A-PTB19-Pad65)") (class "Default")
      (node (ref "IC1") (pin "65") (pinfunction "PTB19_65") (pintype "bidirectional"))
    )
    (net (code "88") (name "unconnected-(IC1A-PTB20-Pad66)") (class "Default")
      (node (ref "IC1") (pin "66") (pinfunction "PTB20_66") (pintype "bidirectional"))
    )
    (net (code "89") (name "unconnected-(IC1A-PTC0-Pad70)") (class "Default")
      (node (ref "IC1") (pin "70") (pinfunction "PTC0_70") (pintype "bidirectional"))
    )
    (net (code "90") (name "unconnected-(IC1A-PTC1-Pad71)") (class "Default")
      (node (ref "IC1") (pin "71") (pinfunction "PTC1_71") (pintype "bidirectional"))
    )
    (net (code "91") (name "unconnected-(IC1A-PTC2-Pad72)") (class "Default")
      (node (ref "IC1") (pin "72") (pinfunction "PTC2_72") (pintype "bidirectional"))
    )
    (net (code "92") (name "unconnected-(IC1A-PTC6-Pad78)") (class "Default")
      (node (ref "IC1") (pin "78") (pinfunction "PTC6_78") (pintype "bidirectional"))
    )
    (net (code "93") (name "unconnected-(IC1A-PTC7-Pad79)") (class "Default")
      (node (ref "IC1") (pin "79") (pinfunction "PTC7_79") (pintype "bidirectional"))
    )
    (net (code "94") (name "unconnected-(IC1A-PTC8-Pad80)") (class "Default")
      (node (ref "IC1") (pin "80") (pinfunction "PTC8_80") (pintype "bidirectional"))
    )
    (net (code "95") (name "unconnected-(IC1A-PTC9-Pad81)") (class "Default")
      (node (ref "IC1") (pin "81") (pinfunction "PTC9_81") (pintype "bidirectional"))
    )
    (net (code "96") (name "unconnected-(IC1A-PTC10-Pad82)") (class "Default")
      (node (ref "IC1") (pin "82") (pinfunction "PTC10_82") (pintype "bidirectional"))
    )
    (net (code "97") (name "unconnected-(IC1A-PTC11-Pad83)") (class "Default")
      (node (ref "IC1") (pin "83") (pinfunction "PTC11_83") (pintype "bidirectional"))
    )
    (net (code "98") (name "unconnected-(IC1A-PTC12-Pad84)") (class "Default")
      (node (ref "IC1") (pin "84") (pinfunction "PTC12_84") (pintype "bidirectional"))
    )
    (net (code "99") (name "unconnected-(IC1A-PTC13-Pad85)") (class "Default")
      (node (ref "IC1") (pin "85") (pinfunction "PTC13_85") (pintype "bidirectional"))
    )
    (net (code "100") (name "unconnected-(IC1A-PTC14-Pad86)") (class "Default")
      (node (ref "IC1") (pin "86") (pinfunction "PTC14_86") (pintype "bidirectional"))
    )
    (net (code "101") (name "unconnected-(IC1A-PTC15-Pad87)") (class "Default")
      (node (ref "IC1") (pin "87") (pinfunction "PTC15_87") (pintype "bidirectional"))
    )
    (net (code "102") (name "unconnected-(IC1A-PTC16-Pad90)") (class "Default")
      (node (ref "IC1") (pin "90") (pinfunction "PTC16_90") (pintype "bidirectional"))
    )
    (net (code "103") (name "unconnected-(IC1A-PTC17-Pad91)") (class "Default")
      (node (ref "IC1") (pin "91") (pinfunction "PTC17_91") (pintype "bidirectional"))
    )
    (net (code "104") (name "unconnected-(IC1A-PTC18-Pad92)") (class "Default")
      (node (ref "IC1") (pin "92") (pinfunction "PTC18_92") (pintype "bidirectional"))
    )
    (net (code "105") (name "unconnected-(IC1A-PTD5-Pad98)") (class "Default")
      (node (ref "IC1") (pin "98") (pinfunction "PTD5_98") (pintype "bidirectional"))
    )
    (net (code "106") (name "unconnected-(IC1A-PTD6-Pad99)") (class "Default")
      (node (ref "IC1") (pin "99") (pinfunction "PTD6_99") (pintype "bidirectional"))
    )
    (net (code "107") (name "unconnected-(IC1A-PTD7-Pad100)") (class "Default")
      (node (ref "IC1") (pin "100") (pinfunction "PTD7_100") (pintype "bidirectional"))
    )
    (net (code "108") (name "unconnected-(IC1A-PTE4-Pad5)") (class "Default")
      (node (ref "IC1") (pin "5") (pinfunction "PTE4_5") (pintype "bidirectional"))
    )
    (net (code "109") (name "unconnected-(IC1A-PTE5-Pad6)") (class "Default")
      (node (ref "IC1") (pin "6") (pinfunction "PTE5_6") (pintype "bidirectional"))
    )
    (net (code "110") (name "unconnected-(IC1A-PTE6-Pad7)") (class "Default")
      (node (ref "IC1") (pin "7") (pinfunction "PTE6_7") (pintype "bidirectional"))
    )
    (net (code "111") (name "unconnected-(IC1A-USB0_DM-Pad11)") (class "Default")
      (node (ref "IC1") (pin "11") (pinfunction "USB0_DM_11") (pintype "bidirectional"))
    )
    (net (code "112") (name "unconnected-(IC1A-USB0_DP-Pad10)") (class "Default")
      (node (ref "IC1") (pin "10") (pinfunction "USB0_DP_10") (pintype "bidirectional"))
    )
    (net (code "113") (name "unconnected-(IC1B-DAC0_OUT-Pad27)") (class "Default")
      (node (ref "IC1") (pin "27") (pinfunction "DAC0_OUT_27") (pintype "bidirectional"))
    )
    (net (code "114") (name "unconnected-(IC1B-VREF_OUT-Pad26)") (class "Default")
      (node (ref "IC1") (pin "26") (pinfunction "VREF_OUT_26") (pintype "bidirectional"))
    )
    (net (code "115") (name "unconnected-(IC1B-XTAL0-Pad51)") (class "Default")
      (node (ref "IC1") (pin "51") (pinfunction "XTAL0_51") (pintype "bidirectional"))
    )
    (net (code "116") (name "unconnected-(IC2-PIO0_4{slash}SCL-Pad10)") (class "Default")
      (node (ref "IC2") (pin "10") (pinfunction "PIO0_4/SCL_10") (pintype "bidirectional"))
    )
    (net (code "117") (name "unconnected-(IC2-PIO0_5{slash}SDA-Pad11)") (class "Default")
      (node (ref "IC2") (pin "11") (pinfunction "PIO0_5/SDA_11") (pintype "bidirectional"))
    )
    (net (code "118") (name "unconnected-(IC2-PIO0_16{slash}AD5{slash}CT32B1_MAT3{slash}WAKEUP-Pad26)") (class "Default")
      (node (ref "IC2") (pin "26") (pinfunction "PIO0_16/AD5/CT32B1_MAT3/WAKEUP_26") (pintype "bidirectional"))
    )
    (net (code "119") (name "unconnected-(IC2-PIO0_23{slash}AD7-Pad27)") (class "Default")
      (node (ref "IC2") (pin "27") (pinfunction "PIO0_23/AD7_27") (pintype "bidirectional"))
    )
    (net (code "120") (name "unconnected-(IC2-PIO1_15{slash}~{DCD}{slash}CT16B0_MAT2{slash}SCK1-Pad28)") (class "Default")
      (node (ref "IC2") (pin "28") (pinfunction "PIO1_15/~{DCD}/CT16B0_MAT2/SCK1_28") (pintype "bidirectional"))
    )
    (net (code "121") (name "unconnected-(IC2-SWCLK{slash}PIO0_10{slash}SCK0{slash}CT16B0_MAT2-Pad19)") (class "Default")
      (node (ref "IC2") (pin "19") (pinfunction "SWCLK/PIO0_10/SCK0/CT16B0_MAT2_19") (pintype "bidirectional"))
    )
    (net (code "122") (name "unconnected-(IC2-SWDIO{slash}PIO0_15{slash}AD4{slash}CT32B1_MAT2-Pad25)") (class "Default")
      (node (ref "IC2") (pin "25") (pinfunction "SWDIO/PIO0_15/AD4/CT32B1_MAT2_25") (pintype "bidirectional"))
    )
    (net (code "123") (name "unconnected-(IC2-TDO{slash}PIO0_13{slash}AD2{slash}CT32B1_MAT0-Pad23)") (class "Default")
      (node (ref "IC2") (pin "23") (pinfunction "TDO/PIO0_13/AD2/CT32B1_MAT0_23") (pintype "bidirectional"))
    )
    (net (code "124") (name "unconnected-(IC2-TMS{slash}PIO0_12{slash}AD1{slash}CT32B1_CAP0-Pad22)") (class "Default")
      (node (ref "IC2") (pin "22") (pinfunction "TMS/PIO0_12/AD1/CT32B1_CAP0_22") (pintype "bidirectional"))
    )
    (net (code "125") (name "unconnected-(IC2-~{TRST}{slash}PIO0_14{slash}AD3{slash}CT32B1_MAT1-Pad24)") (class "Default")
      (node (ref "IC2") (pin "24") (pinfunction "~{TRST}/PIO0_14/AD3/CT32B1_MAT1_24") (pintype "bidirectional"))
    )
    (net (code "126") (name "unconnected-(MOD1-CLKM-Pad39)") (class "Default")
      (node (ref "MOD1") (pin "39") (pinfunction "CLKM_39") (pintype "bidirectional"))
    )
  )
)
